# Sheet1.net
KiCad netlist of a schematic drawn in Altium Designer
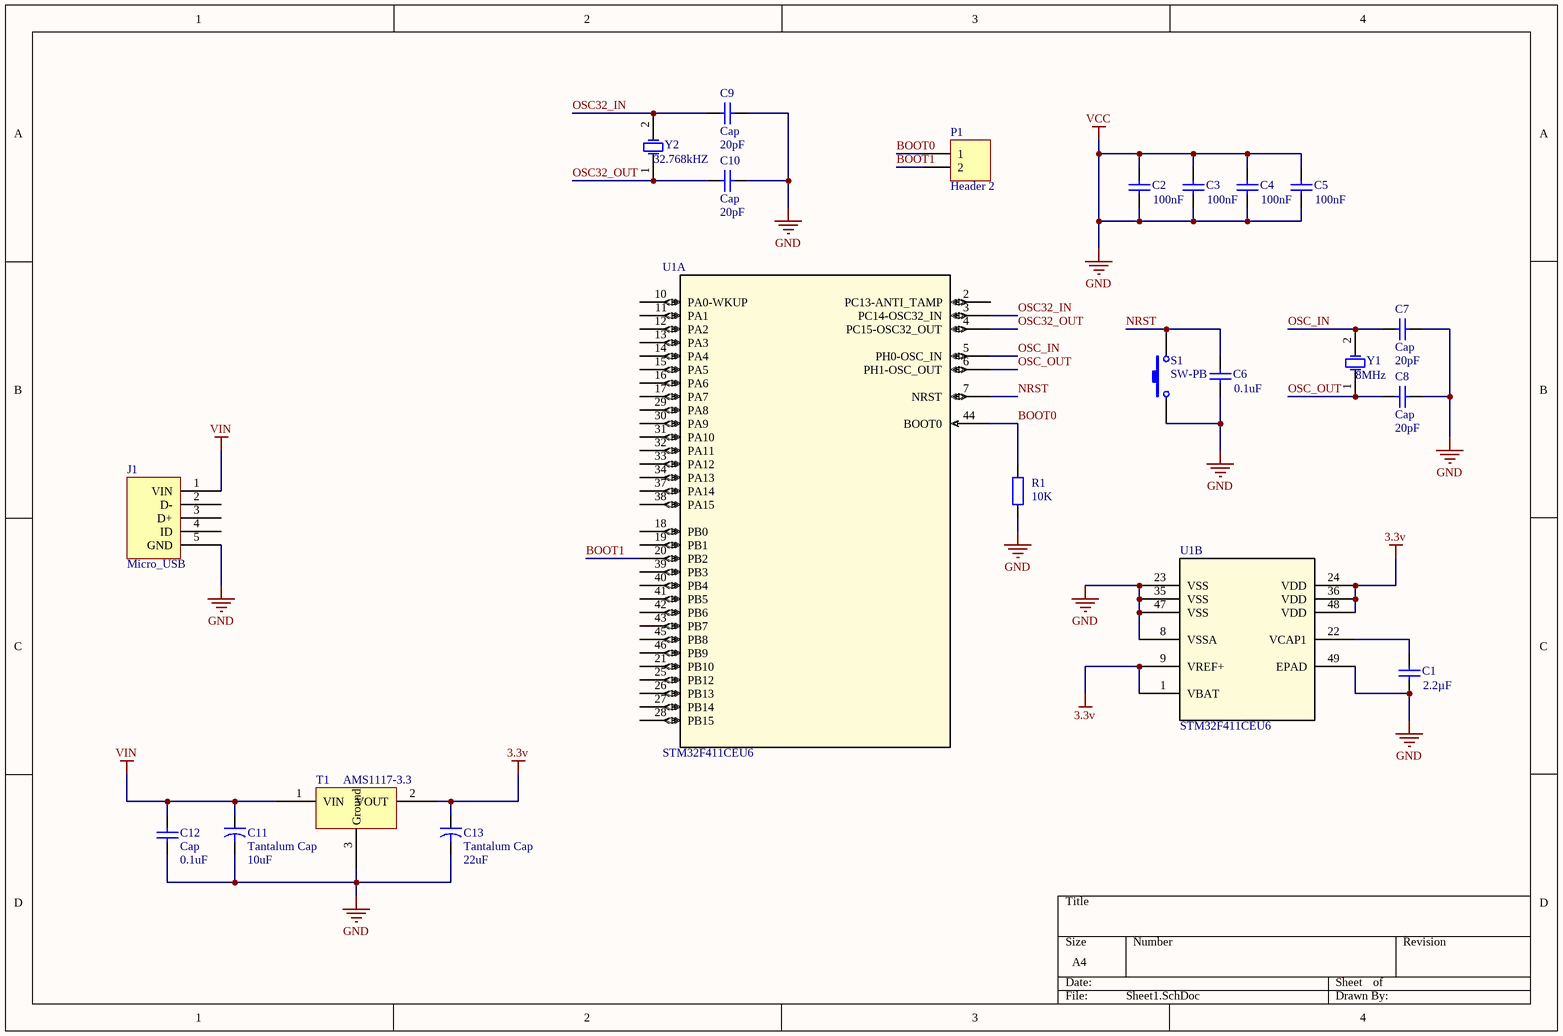
[diagram p0: Sheet1.SchDoc]

(export (version "E")
  (design (tool "Eeschema 10.0.6"))
  (components
    (comp (ref "C1")
      (value "2.2µF")
      (footprint "RAD-0.3")
      (description "Capacitor")
      (fields (field (name "Comment") "Cap") (field (name "PUBLISHER") "Altium Limited"))
      (libsource (lib "Miscellaneous Devices") (part "Cap"))
    )
    (comp (ref "C2")
      (value "100nF")
      (footprint "RAD-0.3")
      (description "Capacitor")
      (fields (field (name "Comment") "Cap") (field (name "PUBLISHER") "Altium Limited"))
      (libsource (lib "Miscellaneous Devices") (part "Cap"))
    )
    (comp (ref "C3")
      (value "100nF")
      (footprint "RAD-0.3")
      (description "Capacitor")
      (fields (field (name "Comment") "Cap") (field (name "PUBLISHER") "Altium Limited"))
      (libsource (lib "Miscellaneous Devices") (part "Cap"))
    )
    (comp (ref "C4")
      (value "100nF")
      (footprint "RAD-0.3")
      (description "Capacitor")
      (fields (field (name "Comment") "Cap") (field (name "PUBLISHER") "Altium Limited"))
      (libsource (lib "Miscellaneous Devices") (part "Cap"))
    )
    (comp (ref "C5")
      (value "100nF")
      (footprint "RAD-0.3")
      (description "Capacitor")
      (fields (field (name "Comment") "Cap") (field (name "PUBLISHER") "Altium Limited"))
      (libsource (lib "Miscellaneous Devices") (part "Cap"))
    )
    (comp (ref "C6")
      (value "0.1uF")
      (footprint "RAD-0.3")
      (description "Capacitor")
      (fields (field (name "Comment") "Cap") (field (name "PUBLISHER") "Altium Limited"))
      (libsource (lib "Miscellaneous Devices") (part "Cap"))
    )
    (comp (ref "C7")
      (value "Cap")
      (footprint "RAD-0.3")
      (description "Capacitor")
      (fields (field (name "ALTIUM_VALUE") "20pF") (field (name "PUBLISHER") "Altium Limited"))
      (libsource (lib "Miscellaneous Devices") (part "Cap"))
    )
    (comp (ref "C8")
      (value "Cap")
      (footprint "RAD-0.3")
      (description "Capacitor")
      (fields (field (name "ALTIUM_VALUE") "20pF") (field (name "PUBLISHER") "Altium Limited"))
      (libsource (lib "Miscellaneous Devices") (part "Cap"))
    )
    (comp (ref "C9")
      (value "Cap")
      (footprint "RAD-0.3")
      (description "Capacitor")
      (fields (field (name "ALTIUM_VALUE") "20pF") (field (name "PUBLISHER") "Altium Limited"))
      (libsource (lib "Miscellaneous Devices") (part "Cap"))
    )
    (comp (ref "C10")
      (value "Cap")
      (footprint "RAD-0.3")
      (description "Capacitor")
      (fields (field (name "ALTIUM_VALUE") "20pF") (field (name "PUBLISHER") "Altium Limited"))
      (libsource (lib "Miscellaneous Devices") (part "Cap"))
    )
    (comp (ref "C11")
      (value "Tantalum Cap")
      (footprint "CAPR5-4X5")
      (description "Capacitor")
      (fields (field (name "ALTIUM_VALUE") "10uF") (field (name "PUBLISHER") "Altium Limited"))
      (libsource (lib "Miscellaneous Devices") (part "Cap2"))
    )
    (comp (ref "C12")
      (value "Cap")
      (footprint "RAD-0.3")
      (description "Capacitor")
      (fields (field (name "ALTIUM_VALUE") "0.1uF") (field (name "PUBLISHER") "Altium Limited"))
      (libsource (lib "Miscellaneous Devices") (part "Cap"))
    )
    (comp (ref "C13")
      (value "Tantalum Cap")
      (footprint "CAPR5-4X5")
      (description "Capacitor")
      (fields (field (name "ALTIUM_VALUE") "22uF") (field (name "PUBLISHER") "Altium Limited"))
      (libsource (lib "Miscellaneous Devices") (part "Cap2"))
    )
    (comp (ref "J1") (value "Micro_USB") (libsource (lib "STM32F411CEU6") (part "Micro_USB")))
    (comp (ref "P1")
      (value "Header 2")
      (footprint "HDR1X2")
      (description "Header, 2-Pin")
      (fields (field (name "PUBLISHER") "Altium Limited"))
      (libsource (lib "Miscellaneous Connectors") (part "Header 2"))
    )
    (comp (ref "R1")
      (value "10K")
      (footprint "AXIAL-0.4")
      (description "Resistor")
      (fields (field (name "Comment") "Res2") (field (name "PUBLISHER") "Altium Limited"))
      (libsource (lib "Miscellaneous Devices") (part "Res2"))
    )
    (comp (ref "S1")
      (value "SW-PB")
      (footprint "SPST-2")
      (description "Switch")
      (fields (field (name "PUBLISHER") "Altium Limited"))
      (libsource (lib "Miscellaneous Devices") (part "SW-PB"))
    )
    (comp (ref "T1") (value "AMS1117-3.3") (libsource (lib "STM32F411CEU6") (part "AMS1117-3.3")))
    (comp (ref "U1")
      (value "STM32F411CEU6")
      (footprint "UFQFPN-48_7X7X0P55MM")
      (description "No Description Available")
      (fields (field (name "COPYRIGHT") "Copyright (C) 2021 Ultra Librarian. All rights reserved."))
      (libsource (lib "STM32F411CEU6") (part "STM32F411CEU6"))
    )
    (comp (ref "Y1")
      (value "8MHz")
      (footprint "R38")
      (description "Crystal Oscillator")
      (fields (field (name "Comment") "XTAL") (field (name "PUBLISHER") "Altium Limited"))
      (libsource (lib "Miscellaneous Devices") (part "XTAL"))
    )
    (comp (ref "Y2")
      (value "32.768kHZ")
      (footprint "R38")
      (description "Crystal Oscillator")
      (fields (field (name "Comment") "XTAL") (field (name "PUBLISHER") "Altium Limited"))
      (libsource (lib "Miscellaneous Devices") (part "XTAL"))
    )
  )
  (nets
    (net (code "1") (name "/BOOT0") (class "Default")
      (node (ref "P1") (pin "1") (pinfunction "1_1") (pintype "passive"))
      (node (ref "R1") (pin "2") (pinfunction "2_2") (pintype "passive"))
      (node (ref "U1") (pin "44") (pinfunction "BOOT0_44") (pintype "input"))
    )
    (net (code "2") (name "/BOOT1") (class "Default")
      (node (ref "P1") (pin "2") (pinfunction "2_2") (pintype "passive"))
      (node (ref "U1") (pin "20") (pinfunction "PB2_20") (pintype "bidirectional"))
    )
    (net (code "3") (name "/NRST") (class "Default")
      (node (ref "C6") (pin "2") (pinfunction "2_2") (pintype "passive"))
      (node (ref "S1") (pin "2") (pinfunction "2_2") (pintype "passive"))
      (node (ref "U1") (pin "7") (pinfunction "NRST_7") (pintype "bidirectional"))
    )
    (net (code "4") (name "/OSC32_IN") (class "Default")
      (node (ref "C9") (pin "1") (pinfunction "1_1") (pintype "passive"))
      (node (ref "U1") (pin "3") (pinfunction "PC14-OSC32_IN_3") (pintype "bidirectional"))
      (node (ref "Y2") (pin "2") (pinfunction "OSC2_2") (pintype "passive"))
    )
    (net (code "5") (name "/OSC32_OUT") (class "Default")
      (node (ref "C10") (pin "1") (pinfunction "1_1") (pintype "passive"))
      (node (ref "U1") (pin "4") (pinfunction "PC15-OSC32_OUT_4") (pintype "bidirectional"))
      (node (ref "Y2") (pin "1") (pinfunction "OSC1_1") (pintype "passive"))
    )
    (net (code "6") (name "/OSC_IN") (class "Default")
      (node (ref "C7") (pin "1") (pinfunction "1_1") (pintype "passive"))
      (node (ref "U1") (pin "5") (pinfunction "PH0-OSC_IN_5") (pintype "bidirectional"))
      (node (ref "Y1") (pin "2") (pinfunction "OSC2_2") (pintype "passive"))
    )
    (net (code "7") (name "/OSC_OUT") (class "Default")
      (node (ref "C8") (pin "1") (pinfunction "1_1") (pintype "passive"))
      (node (ref "U1") (pin "6") (pinfunction "PH1-OSC_OUT_6") (pintype "bidirectional"))
      (node (ref "Y1") (pin "1") (pinfunction "OSC1_1") (pintype "passive"))
    )
    (net (code "8") (name "3.3v") (class "Default")
      (node (ref "C13") (pin "1") (pinfunction "1_1") (pintype "passive"))
      (node (ref "T1") (pin "2") (pinfunction "VOUT_2") (pintype "passive"))
      (node (ref "U1") (pin "1") (pinfunction "VBAT_1") (pintype "power_in"))
      (node (ref "U1") (pin "24") (pinfunction "VDD_24") (pintype "power_in"))
      (node (ref "U1") (pin "36") (pinfunction "VDD_36") (pintype "power_in"))
      (node (ref "U1") (pin "48") (pinfunction "VDD_48") (pintype "power_in"))
      (node (ref "U1") (pin "9") (pinfunction "VREF+_9") (pintype "power_in"))
    )
    (net (code "9") (name "GND") (class "Default")
      (node (ref "C1") (pin "1") (pinfunction "1_1") (pintype "passive"))
      (node (ref "C10") (pin "2") (pinfunction "2_2") (pintype "passive"))
      (node (ref "C11") (pin "2") (pinfunction "2_2") (pintype "passive"))
      (node (ref "C12") (pin "1") (pinfunction "1_1") (pintype "passive"))
      (node (ref "C13") (pin "2") (pinfunction "2_2") (pintype "passive"))
      (node (ref "C2") (pin "1") (pinfunction "1_1") (pintype "passive"))
      (node (ref "C2") (pin "2") (pinfunction "2_2") (pintype "passive"))
      (node (ref "C3") (pin "1") (pinfunction "1_1") (pintype "passive"))
      (node (ref "C3") (pin "2") (pinfunction "2_2") (pintype "passive"))
      (node (ref "C4") (pin "1") (pinfunction "1_1") (pintype "passive"))
      (node (ref "C4") (pin "2") (pinfunction "2_2") (pintype "passive"))
      (node (ref "C5") (pin "1") (pinfunction "1_1") (pintype "passive"))
      (node (ref "C5") (pin "2") (pinfunction "2_2") (pintype "passive"))
      (node (ref "C6") (pin "1") (pinfunction "1_1") (pintype "passive"))
      (node (ref "C7") (pin "2") (pinfunction "2_2") (pintype "passive"))
      (node (ref "C8") (pin "2") (pinfunction "2_2") (pintype "passive"))
      (node (ref "C9") (pin "2") (pinfunction "2_2") (pintype "passive"))
      (node (ref "J1") (pin "5") (pinfunction "GND_5") (pintype "passive"))
      (node (ref "R1") (pin "1") (pinfunction "1_1") (pintype "passive"))
      (node (ref "S1") (pin "1") (pinfunction "1_1") (pintype "passive"))
      (node (ref "T1") (pin "3") (pinfunction "Ground_3") (pintype "passive"))
      (node (ref "U1") (pin "23") (pinfunction "VSS_23") (pintype "power_in"))
      (node (ref "U1") (pin "35") (pinfunction "VSS_35") (pintype "power_in"))
      (node (ref "U1") (pin "47") (pinfunction "VSS_47") (pintype "power_in"))
      (node (ref "U1") (pin "49") (pinfunction "EPAD_49") (pintype "passive"))
      (node (ref "U1") (pin "8") (pinfunction "VSSA_8") (pintype "power_in"))
    )
    (net (code "10") (name "Net-(U1B-VCAP1)") (class "Default")
      (node (ref "C1") (pin "2") (pinfunction "2_2") (pintype "passive"))
      (node (ref "U1") (pin "22") (pinfunction "VCAP1_22") (pintype "power_in"))
    )
    (net (code "11") (name "VIN") (class "Default")
      (node (ref "C11") (pin "1") (pinfunction "1_1") (pintype "passive"))
      (node (ref "C12") (pin "2") (pinfunction "2_2") (pintype "passive"))
      (node (ref "J1") (pin "1") (pinfunction "VIN_1") (pintype "passive"))
      (node (ref "T1") (pin "1") (pinfunction "VIN_1") (pintype "passive"))
    )
    (net (code "12") (name "unconnected-(J1-D+-Pad3)") (class "Default")
      (node (ref "J1") (pin "3") (pinfunction "D+_3") (pintype "passive"))
    )
    (net (code "13") (name "unconnected-(J1-D--Pad2)") (class "Default")
      (node (ref "J1") (pin "2") (pinfunction "D-_2") (pintype "passive"))
    )
    (net (code "14") (name "unconnected-(J1-ID-Pad4)") (class "Default")
      (node (ref "J1") (pin "4") (pinfunction "ID_4") (pintype "passive"))
    )
    (net (code "15") (name "unconnected-(U1A-PA0-WKUP-Pad10)") (class "Default")
      (node (ref "U1") (pin "10") (pinfunction "PA0-WKUP_10") (pintype "bidirectional"))
    )
    (net (code "16") (name "unconnected-(U1A-PA1-Pad11)") (class "Default")
      (node (ref "U1") (pin "11") (pinfunction "PA1_11") (pintype "bidirectional"))
    )
    (net (code "17") (name "unconnected-(U1A-PA2-Pad12)") (class "Default")
      (node (ref "U1") (pin "12") (pinfunction "PA2_12") (pintype "bidirectional"))
    )
    (net (code "18") (name "unconnected-(U1A-PA3-Pad13)") (class "Default")
      (node (ref "U1") (pin "13") (pinfunction "PA3_13") (pintype "bidirectional"))
    )
    (net (code "19") (name "unconnected-(U1A-PA4-Pad14)") (class "Default")
      (node (ref "U1") (pin "14") (pinfunction "PA4_14") (pintype "bidirectional"))
    )
    (net (code "20") (name "unconnected-(U1A-PA5-Pad15)") (class "Default")
      (node (ref "U1") (pin "15") (pinfunction "PA5_15") (pintype "bidirectional"))
    )
    (net (code "21") (name "unconnected-(U1A-PA6-Pad16)") (class "Default")
      (node (ref "U1") (pin "16") (pinfunction "PA6_16") (pintype "bidirectional"))
    )
    (net (code "22") (name "unconnected-(U1A-PA7-Pad17)") (class "Default")
      (node (ref "U1") (pin "17") (pinfunction "PA7_17") (pintype "bidirectional"))
    )
    (net (code "23") (name "unconnected-(U1A-PA8-Pad29)") (class "Default")
      (node (ref "U1") (pin "29") (pinfunction "PA8_29") (pintype "bidirectional"))
    )
    (net (code "24") (name "unconnected-(U1A-PA9-Pad30)") (class "Default")
      (node (ref "U1") (pin "30") (pinfunction "PA9_30") (pintype "bidirectional"))
    )
    (net (code "25") (name "unconnected-(U1A-PA10-Pad31)") (class "Default")
      (node (ref "U1") (pin "31") (pinfunction "PA10_31") (pintype "bidirectional"))
    )
    (net (code "26") (name "unconnected-(U1A-PA11-Pad32)") (class "Default")
      (node (ref "U1") (pin "32") (pinfunction "PA11_32") (pintype "bidirectional"))
    )
    (net (code "27") (name "unconnected-(U1A-PA12-Pad33)") (class "Default")
      (node (ref "U1") (pin "33") (pinfunction "PA12_33") (pintype "bidirectional"))
    )
    (net (code "28") (name "unconnected-(U1A-PA13-Pad34)") (class "Default")
      (node (ref "U1") (pin "34") (pinfunction "PA13_34") (pintype "bidirectional"))
    )
    (net (code "29") (name "unconnected-(U1A-PA14-Pad37)") (class "Default")
      (node (ref "U1") (pin "37") (pinfunction "PA14_37") (pintype "bidirectional"))
    )
    (net (code "30") (name "unconnected-(U1A-PA15-Pad38)") (class "Default")
      (node (ref "U1") (pin "38") (pinfunction "PA15_38") (pintype "bidirectional"))
    )
    (net (code "31") (name "unconnected-(U1A-PB0-Pad18)") (class "Default")
      (node (ref "U1") (pin "18") (pinfunction "PB0_18") (pintype "bidirectional"))
    )
    (net (code "32") (name "unconnected-(U1A-PB1-Pad19)") (class "Default")
      (node (ref "U1") (pin "19") (pinfunction "PB1_19") (pintype "bidirectional"))
    )
    (net (code "33") (name "unconnected-(U1A-PB3-Pad39)") (class "Default")
      (node (ref "U1") (pin "39") (pinfunction "PB3_39") (pintype "bidirectional"))
    )
    (net (code "34") (name "unconnected-(U1A-PB4-Pad40)") (class "Default")
      (node (ref "U1") (pin "40") (pinfunction "PB4_40") (pintype "bidirectional"))
    )
    (net (code "35") (name "unconnected-(U1A-PB5-Pad41)") (class "Default")
      (node (ref "U1") (pin "41") (pinfunction "PB5_41") (pintype "bidirectional"))
    )
    (net (code "36") (name "unconnected-(U1A-PB6-Pad42)") (class "Default")
      (node (ref "U1") (pin "42") (pinfunction "PB6_42") (pintype "bidirectional"))
    )
    (net (code "37") (name "unconnected-(U1A-PB7-Pad43)") (class "Default")
      (node (ref "U1") (pin "43") (pinfunction "PB7_43") (pintype "bidirectional"))
    )
    (net (code "38") (name "unconnected-(U1A-PB8-Pad45)") (class "Default")
      (node (ref "U1") (pin "45") (pinfunction "PB8_45") (pintype "bidirectional"))
    )
    (net (code "39") (name "unconnected-(U1A-PB9-Pad46)") (class "Default")
      (node (ref "U1") (pin "46") (pinfunction "PB9_46") (pintype "bidirectional"))
    )
    (net (code "40") (name "unconnected-(U1A-PB10-Pad21)") (class "Default")
      (node (ref "U1") (pin "21") (pinfunction "PB10_21") (pintype "bidirectional"))
    )
    (net (code "41") (name "unconnected-(U1A-PB12-Pad25)") (class "Default")
      (node (ref "U1") (pin "25") (pinfunction "PB12_25") (pintype "bidirectional"))
    )
    (net (code "42") (name "unconnected-(U1A-PB13-Pad26)") (class "Default")
      (node (ref "U1") (pin "26") (pinfunction "PB13_26") (pintype "bidirectional"))
    )
    (net (code "43") (name "unconnected-(U1A-PB14-Pad27)") (class "Default")
      (node (ref "U1") (pin "27") (pinfunction "PB14_27") (pintype "bidirectional"))
    )
    (net (code "44") (name "unconnected-(U1A-PB15-Pad28)") (class "Default")
      (node (ref "U1") (pin "28") (pinfunction "PB15_28") (pintype "bidirectional"))
    )
    (net (code "45") (name "unconnected-(U1A-PC13-ANTI_TAMP-Pad2)") (class "Default")
      (node (ref "U1") (pin "2") (pinfunction "PC13-ANTI_TAMP_2") (pintype "bidirectional"))
    )
  )
)
